# LM386_BOARD.net
KiCad netlist of a schematic drawn in EAGLE
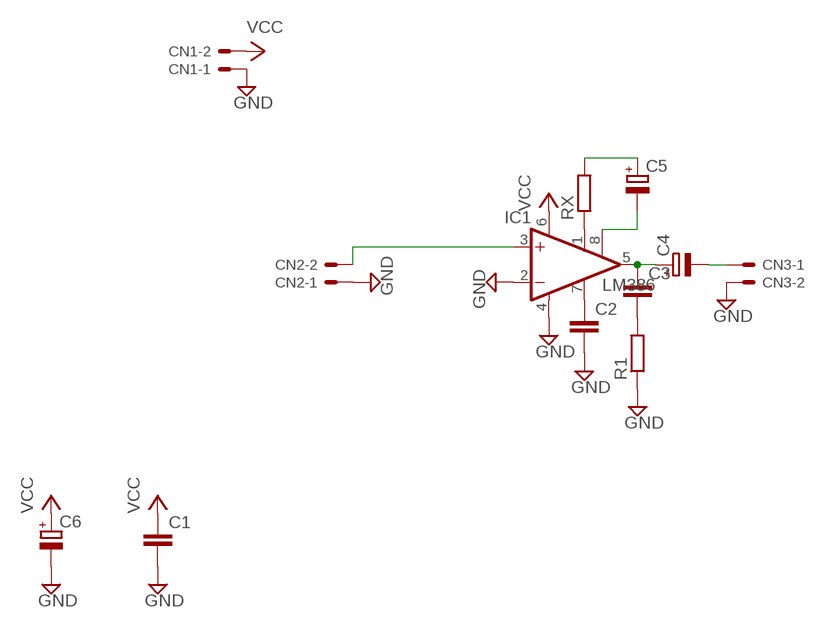
[diagram p0: schematic, sheet 1]

(export (version "E")
  (design (tool "Eeschema 10.0.6"))
  (components
    (comp (ref "C1")
      (value "C-EUC0402K")
      (footprint "eagle-import:C0402K")
      (libsource (lib "eagle-import") (part "C-EUC0402K"))
    )
    (comp (ref "C2")
      (value "C-EUC0402K")
      (footprint "eagle-import:C0402K")
      (libsource (lib "eagle-import") (part "C-EUC0402K"))
    )
    (comp (ref "C3")
      (value "C-EUC0402K")
      (footprint "eagle-import:C0402K")
      (libsource (lib "eagle-import") (part "C-EUC0402K"))
    )
    (comp (ref "C4")
      (value "CPOL-EU153CLV-0505")
      (footprint "eagle-import:153CLV-0505")
      (libsource (lib "eagle-import") (part "CPOL-EU153CLV-0505"))
    )
    (comp (ref "C5")
      (value "CPOL-EU153CLV-0505")
      (footprint "eagle-import:153CLV-0505")
      (libsource (lib "eagle-import") (part "CPOL-EU153CLV-0505"))
    )
    (comp (ref "C6")
      (value "CPOL-EU153CLV-0505")
      (footprint "eagle-import:153CLV-0505")
      (libsource (lib "eagle-import") (part "CPOL-EU153CLV-0505"))
    )
    (comp (ref "CN1")
      (value "22-23-2021")
      (footprint "eagle-import:22-23-2021")
      (fields (field (name "MF") "MOLEX"))
      (libsource (lib "eagle-import") (part "22-23-2021"))
    )
    (comp (ref "CN2")
      (value "22-23-2021")
      (footprint "eagle-import:22-23-2021")
      (fields (field (name "MF") "MOLEX"))
      (libsource (lib "eagle-import") (part "22-23-2021"))
    )
    (comp (ref "CN3")
      (value "22-23-2021")
      (footprint "eagle-import:22-23-2021")
      (fields (field (name "MF") "MOLEX"))
      (libsource (lib "eagle-import") (part "22-23-2021"))
    )
    (comp (ref "IC1")
      (value "LM386")
      (footprint "eagle-import:SO08")
      (libsource (lib "eagle-import") (part "LM386?-M1"))
    )
    (comp (ref "R1")
      (value "R-EU_R0805")
      (footprint "eagle-import:R0805")
      (libsource (lib "eagle-import") (part "R-EU_R0805"))
    )
    (comp (ref "RX")
      (value "R-EU_R0805")
      (footprint "eagle-import:R0805")
      (libsource (lib "eagle-import") (part "R-EU_R0805"))
    )
  )
  (nets
    (net (code "1") (name "GND") (class "Default")
      (node (ref "C1") (pin "2") (pinfunction "2_2") (pintype "passive"))
      (node (ref "C2") (pin "2") (pinfunction "2_2") (pintype "passive"))
      (node (ref "C6") (pin "-") (pinfunction "-_-") (pintype "passive"))
      (node (ref "CN1") (pin "1") (pinfunction "S_1") (pintype "passive"))
      (node (ref "CN2") (pin "1") (pinfunction "S_1") (pintype "passive"))
      (node (ref "CN3") (pin "2") (pinfunction "S_2") (pintype "passive"))
      (node (ref "IC1") (pin "2") (pinfunction "-IN_2") (pintype "input"))
      (node (ref "IC1") (pin "4") (pinfunction "GND_4") (pintype "power_in"))
      (node (ref "R1") (pin "1") (pinfunction "1_1") (pintype "passive"))
    )
    (net (code "2") (name "Net-(C3-Pad2)") (class "Default")
      (node (ref "C3") (pin "2") (pinfunction "2_2") (pintype "passive"))
      (node (ref "R1") (pin "2") (pinfunction "2_2") (pintype "passive"))
    )
    (net (code "3") (name "Net-(C5-Pad+)") (class "Default")
      (node (ref "C5") (pin "+") (pinfunction "+_+") (pintype "passive"))
      (node (ref "RX") (pin "2") (pinfunction "2_2") (pintype "passive"))
    )
    (net (code "4") (name "Net-(C5-Pad-)") (class "Default")
      (node (ref "C5") (pin "-") (pinfunction "-_-") (pintype "passive"))
      (node (ref "IC1") (pin "8") (pinfunction "GAIN_8") (pintype "passive"))
    )
    (net (code "5") (name "Net-(CN2B-S)") (class "Default")
      (node (ref "CN2") (pin "2") (pinfunction "S_2") (pintype "passive"))
      (node (ref "IC1") (pin "3") (pinfunction "+IN_3") (pintype "input"))
    )
    (net (code "6") (name "Net-(CN3A-S)") (class "Default")
      (node (ref "C4") (pin "-") (pinfunction "-_-") (pintype "passive"))
      (node (ref "CN3") (pin "1") (pinfunction "S_1") (pintype "passive"))
    )
    (net (code "7") (name "Net-(IC1-BYPASS)") (class "Default")
      (node (ref "C2") (pin "1") (pinfunction "1_1") (pintype "passive"))
      (node (ref "IC1") (pin "7") (pinfunction "BYPASS_7") (pintype "passive"))
    )
    (net (code "8") (name "Net-(IC1-GAIN-Pad1)") (class "Default")
      (node (ref "IC1") (pin "1") (pinfunction "GAIN_1") (pintype "passive"))
      (node (ref "RX") (pin "1") (pinfunction "1_1") (pintype "passive"))
    )
    (net (code "9") (name "Net-(IC1-OUT)") (class "Default")
      (node (ref "C3") (pin "1") (pinfunction "1_1") (pintype "passive"))
      (node (ref "C4") (pin "+") (pinfunction "+_+") (pintype "passive"))
      (node (ref "IC1") (pin "5") (pinfunction "OUT_5") (pintype "output"))
    )
    (net (code "10") (name "VCC") (class "Default")
      (node (ref "C1") (pin "1") (pinfunction "1_1") (pintype "passive"))
      (node (ref "C6") (pin "+") (pinfunction "+_+") (pintype "passive"))
      (node (ref "CN1") (pin "2") (pinfunction "S_2") (pintype "passive"))
      (node (ref "IC1") (pin "6") (pinfunction "VS_6") (pintype "power_in"))
    )
  )
)
